# EspBreakoutBoard.net
KiCad netlist of a schematic drawn in EAGLE
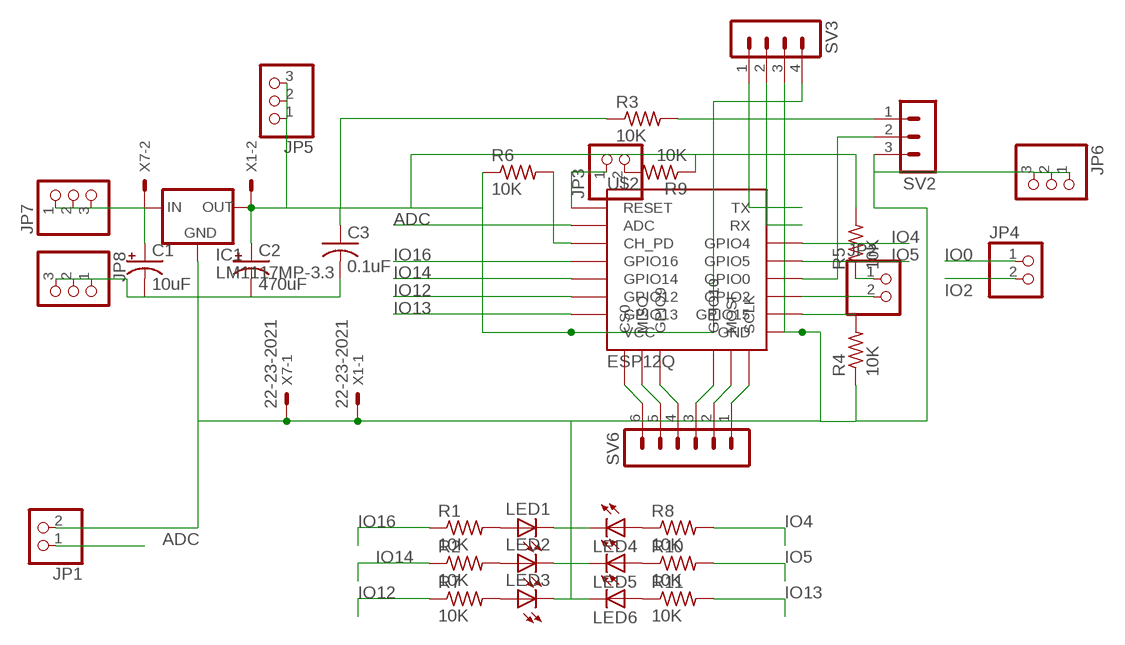
[diagram p0: schematic, sheet 1]

(export (version "E")
  (design (tool "Eeschema 10.0.6"))
  (components
    (comp (ref "C1")
      (value "10uF")
      (footprint "eagle-import:E2,5-6")
      (libsource (lib "eagle-import") (part "CPOL-USE2.5-6"))
    )
    (comp (ref "C2")
      (value "470uF")
      (footprint "eagle-import:E5-8,5")
      (libsource (lib "eagle-import") (part "CPOL-USE5-8.5"))
    )
    (comp (ref "C3")
      (value "0.1uF")
      (footprint "eagle-import:C025-040X050")
      (libsource (lib "eagle-import") (part "C-US025-040X050"))
    )
    (comp (ref "IC1")
      (value "LM1117MP-3.3")
      (footprint "eagle-import:SOT223")
      (fields (field (name "MF") "Texas Instruments"))
      (libsource (lib "eagle-import") (part "LM1117?-MP3.3"))
    )
    (comp (ref "JP1")
      (value "PINHD-1X2")
      (footprint "eagle-import:1X02")
      (libsource (lib "eagle-import") (part "PINHD-1X2"))
    )
    (comp (ref "JP2")
      (value "PINHD-1X2")
      (footprint "eagle-import:1X02")
      (libsource (lib "eagle-import") (part "PINHD-1X2"))
    )
    (comp (ref "JP3")
      (value "PINHD-1X2")
      (footprint "eagle-import:1X02")
      (libsource (lib "eagle-import") (part "PINHD-1X2"))
    )
    (comp (ref "JP4")
      (value "PINHD-1X2")
      (footprint "eagle-import:1X02")
      (libsource (lib "eagle-import") (part "PINHD-1X2"))
    )
    (comp (ref "JP5")
      (value "PINHD-1X3")
      (footprint "eagle-import:1X03")
      (libsource (lib "eagle-import") (part "PINHD-1X3"))
    )
    (comp (ref "JP6")
      (value "PINHD-1X3")
      (footprint "eagle-import:1X03")
      (libsource (lib "eagle-import") (part "PINHD-1X3"))
    )
    (comp (ref "JP7")
      (value "PINHD-1X3")
      (footprint "eagle-import:1X03")
      (libsource (lib "eagle-import") (part "PINHD-1X3"))
    )
    (comp (ref "JP8")
      (value "PINHD-1X3")
      (footprint "eagle-import:1X03")
      (libsource (lib "eagle-import") (part "PINHD-1X3"))
    )
    (comp (ref "LED1")
      (value "LED3MM")
      (footprint "eagle-import:LED3MM")
      (libsource (lib "eagle-import") (part "LED3MM"))
    )
    (comp (ref "LED2")
      (value "LED3MM")
      (footprint "eagle-import:LED3MM")
      (libsource (lib "eagle-import") (part "LED3MM"))
    )
    (comp (ref "LED3")
      (value "LED3MM")
      (footprint "eagle-import:LED3MM")
      (libsource (lib "eagle-import") (part "LED3MM"))
    )
    (comp (ref "LED4")
      (value "LED3MM")
      (footprint "eagle-import:LED3MM")
      (libsource (lib "eagle-import") (part "LED3MM"))
    )
    (comp (ref "LED5")
      (value "LED3MM")
      (footprint "eagle-import:LED3MM")
      (libsource (lib "eagle-import") (part "LED3MM"))
    )
    (comp (ref "LED6")
      (value "LED3MM")
      (footprint "eagle-import:LED3MM")
      (libsource (lib "eagle-import") (part "LED3MM"))
    )
    (comp (ref "R1")
      (value "10K")
      (footprint "eagle-import:0207_10")
      (libsource (lib "eagle-import") (part "R-US_0207/10"))
    )
    (comp (ref "R2")
      (value "10K")
      (footprint "eagle-import:0207_10")
      (libsource (lib "eagle-import") (part "R-US_0207/10"))
    )
    (comp (ref "R3")
      (value "10K")
      (footprint "eagle-import:0207_10")
      (libsource (lib "eagle-import") (part "R-US_0207/10"))
    )
    (comp (ref "R4")
      (value "10K")
      (footprint "eagle-import:0207_10")
      (libsource (lib "eagle-import") (part "R-US_0207/10"))
    )
    (comp (ref "R5")
      (value "10K")
      (footprint "eagle-import:0207_10")
      (libsource (lib "eagle-import") (part "R-US_0207/10"))
    )
    (comp (ref "R6")
      (value "10K")
      (footprint "eagle-import:0207_10")
      (libsource (lib "eagle-import") (part "R-US_0207/10"))
    )
    (comp (ref "R7")
      (value "10K")
      (footprint "eagle-import:0207_10")
      (libsource (lib "eagle-import") (part "R-US_0207/10"))
    )
    (comp (ref "R8")
      (value "10K")
      (footprint "eagle-import:0207_10")
      (libsource (lib "eagle-import") (part "R-US_0207/10"))
    )
    (comp (ref "R9")
      (value "10K")
      (footprint "eagle-import:0207_10")
      (libsource (lib "eagle-import") (part "R-US_0207/10"))
    )
    (comp (ref "R10")
      (value "10K")
      (footprint "eagle-import:0207_10")
      (libsource (lib "eagle-import") (part "R-US_0207/10"))
    )
    (comp (ref "R11")
      (value "10K")
      (footprint "eagle-import:0207_10")
      (libsource (lib "eagle-import") (part "R-US_0207/10"))
    )
    (comp (ref "SV2")
      (value "MA03-1")
      (footprint "eagle-import:MA03-1")
      (libsource (lib "eagle-import") (part "MA03-1"))
    )
    (comp (ref "SV3")
      (value "MA04-1")
      (footprint "eagle-import:MA04-1")
      (libsource (lib "eagle-import") (part "MA04-1"))
    )
    (comp (ref "SV6")
      (value "MA06-1")
      (footprint "eagle-import:MA06-1")
      (libsource (lib "eagle-import") (part "MA06-1"))
    )
    (comp (ref "U$2")
      (value "ESP12Q")
      (footprint "eagle-import:ESP12Q")
      (libsource (lib "eagle-import") (part "ESP12Q"))
    )
    (comp (ref "X1")
      (value "22-23-2021")
      (footprint "eagle-import:22-23-2021")
      (fields (field (name "MF") "MOLEX"))
      (libsource (lib "eagle-import") (part "22-23-2021"))
    )
    (comp (ref "X7")
      (value "22-23-2021")
      (footprint "eagle-import:22-23-2021")
      (fields (field (name "MF") "MOLEX"))
      (libsource (lib "eagle-import") (part "22-23-2021"))
    )
  )
  (nets
    (net (code "1") (name "/ADC") (class "Default")
      (node (ref "JP1") (pin "1") (pinfunction "1_1") (pintype "passive"))
      (node (ref "U$2") (pin "ADC") (pinfunction "ADC_ADC") (pintype "bidirectional"))
    )
    (net (code "2") (name "/IO0") (class "Default")
      (node (ref "JP4") (pin "1") (pinfunction "1_1") (pintype "passive"))
      (node (ref "SV2") (pin "2") (pinfunction "2_2") (pintype "passive"))
      (node (ref "U$2") (pin "GPIO0") (pinfunction "GPIO0_GPIO0") (pintype "bidirectional"))
    )
    (net (code "3") (name "/IO2") (class "Default")
      (node (ref "JP2") (pin "2") (pinfunction "2_2") (pintype "passive"))
      (node (ref "JP4") (pin "2") (pinfunction "2_2") (pintype "passive"))
      (node (ref "U$2") (pin "GPIO2") (pinfunction "GPIO2_GPIO2") (pintype "bidirectional"))
    )
    (net (code "4") (name "/IO4") (class "Default")
      (node (ref "R8") (pin "2") (pinfunction "2_2") (pintype "passive"))
      (node (ref "U$2") (pin "GPIO4") (pinfunction "GPIO4_GPIO4") (pintype "bidirectional"))
    )
    (net (code "5") (name "/IO5") (class "Default")
      (node (ref "R10") (pin "2") (pinfunction "2_2") (pintype "passive"))
      (node (ref "U$2") (pin "GPIO5") (pinfunction "GPIO5_GPIO5") (pintype "bidirectional"))
    )
    (net (code "6") (name "/IO12") (class "Default")
      (node (ref "R7") (pin "1") (pinfunction "1_1") (pintype "passive"))
      (node (ref "U$2") (pin "GPIO12") (pinfunction "GPIO12_GPIO12") (pintype "bidirectional"))
    )
    (net (code "7") (name "/IO13") (class "Default")
      (node (ref "R11") (pin "2") (pinfunction "2_2") (pintype "passive"))
      (node (ref "U$2") (pin "GPIO13") (pinfunction "GPIO13_GPIO13") (pintype "bidirectional"))
    )
    (net (code "8") (name "/IO14") (class "Default")
      (node (ref "R2") (pin "1") (pinfunction "1_1") (pintype "passive"))
      (node (ref "U$2") (pin "GPIO14") (pinfunction "GPIO14_GPIO14") (pintype "bidirectional"))
    )
    (net (code "9") (name "/IO16") (class "Default")
      (node (ref "R1") (pin "1") (pinfunction "1_1") (pintype "passive"))
      (node (ref "U$2") (pin "GPIO16") (pinfunction "GPIO16_GPIO16") (pintype "bidirectional"))
    )
    (net (code "10") (name "Net-(IC1-GND)") (class "Default")
      (node (ref "C1") (pin "-") (pinfunction "-_-") (pintype "passive"))
      (node (ref "C2") (pin "-") (pinfunction "-_-") (pintype "passive"))
      (node (ref "C3") (pin "2") (pinfunction "2_2") (pintype "passive"))
      (node (ref "IC1") (pin "1") (pinfunction "GND_1") (pintype "input"))
      (node (ref "JP1") (pin "2") (pinfunction "2_2") (pintype "passive"))
      (node (ref "JP6") (pin "1") (pinfunction "1_1") (pintype "passive"))
      (node (ref "JP6") (pin "2") (pinfunction "2_2") (pintype "passive"))
      (node (ref "JP6") (pin "3") (pinfunction "3_3") (pintype "passive"))
      (node (ref "JP8") (pin "1") (pinfunction "1_1") (pintype "passive"))
      (node (ref "JP8") (pin "2") (pinfunction "2_2") (pintype "passive"))
      (node (ref "JP8") (pin "3") (pinfunction "3_3") (pintype "passive"))
      (node (ref "LED1") (pin "K") (pinfunction "C_K") (pintype "passive"))
      (node (ref "LED2") (pin "K") (pinfunction "C_K") (pintype "passive"))
      (node (ref "LED3") (pin "K") (pinfunction "C_K") (pintype "passive"))
      (node (ref "LED4") (pin "K") (pinfunction "C_K") (pintype "passive"))
      (node (ref "LED5") (pin "K") (pinfunction "C_K") (pintype "passive"))
      (node (ref "LED6") (pin "K") (pinfunction "C_K") (pintype "passive"))
      (node (ref "R4") (pin "1") (pinfunction "1_1") (pintype "passive"))
      (node (ref "SV2") (pin "3") (pinfunction "3_3") (pintype "passive"))
      (node (ref "SV3") (pin "3") (pinfunction "3_3") (pintype "passive"))
      (node (ref "U$2") (pin "GND") (pinfunction "GND_GND") (pintype "bidirectional"))
      (node (ref "X1") (pin "1") (pinfunction "S_1") (pintype "passive"))
      (node (ref "X7") (pin "1") (pinfunction "S_1") (pintype "passive"))
    )
    (net (code "11") (name "Net-(IC1-IN)") (class "Default")
      (node (ref "C1") (pin "+") (pinfunction "+_+") (pintype "passive"))
      (node (ref "IC1") (pin "3") (pinfunction "IN_3") (pintype "input"))
      (node (ref "JP7") (pin "1") (pinfunction "1_1") (pintype "passive"))
      (node (ref "JP7") (pin "2") (pinfunction "2_2") (pintype "passive"))
      (node (ref "JP7") (pin "3") (pinfunction "3_3") (pintype "passive"))
      (node (ref "X7") (pin "2") (pinfunction "S_2") (pintype "passive"))
    )
    (net (code "12") (name "Net-(JP2-Pad1)") (class "Default")
      (node (ref "JP2") (pin "1") (pinfunction "1_1") (pintype "passive"))
      (node (ref "R5") (pin "1") (pinfunction "1_1") (pintype "passive"))
    )
    (net (code "13") (name "Net-(JP3-Pad1)") (class "Default")
      (node (ref "JP3") (pin "1") (pinfunction "1_1") (pintype "passive"))
      (node (ref "U$2") (pin "RESET") (pinfunction "RESET_RESET") (pintype "bidirectional"))
    )
    (net (code "14") (name "Net-(JP3-Pad2)") (class "Default")
      (node (ref "JP3") (pin "2") (pinfunction "2_2") (pintype "passive"))
      (node (ref "R9") (pin "2") (pinfunction "2_2") (pintype "passive"))
    )
    (net (code "15") (name "Net-(LED1-PadA)") (class "Default")
      (node (ref "LED1") (pin "A") (pinfunction "A_A") (pintype "passive"))
      (node (ref "R1") (pin "2") (pinfunction "2_2") (pintype "passive"))
    )
    (net (code "16") (name "Net-(LED2-PadA)") (class "Default")
      (node (ref "LED2") (pin "A") (pinfunction "A_A") (pintype "passive"))
      (node (ref "R2") (pin "2") (pinfunction "2_2") (pintype "passive"))
    )
    (net (code "17") (name "Net-(LED3-PadA)") (class "Default")
      (node (ref "LED3") (pin "A") (pinfunction "A_A") (pintype "passive"))
      (node (ref "R7") (pin "2") (pinfunction "2_2") (pintype "passive"))
    )
    (net (code "18") (name "Net-(LED4-PadA)") (class "Default")
      (node (ref "LED4") (pin "A") (pinfunction "A_A") (pintype "passive"))
      (node (ref "R8") (pin "1") (pinfunction "1_1") (pintype "passive"))
    )
    (net (code "19") (name "Net-(LED5-PadA)") (class "Default")
      (node (ref "LED5") (pin "A") (pinfunction "A_A") (pintype "passive"))
      (node (ref "R10") (pin "1") (pinfunction "1_1") (pintype "passive"))
    )
    (net (code "20") (name "Net-(LED6-PadA)") (class "Default")
      (node (ref "LED6") (pin "A") (pinfunction "A_A") (pintype "passive"))
      (node (ref "R11") (pin "1") (pinfunction "1_1") (pintype "passive"))
    )
    (net (code "21") (name "Net-(R3-Pad2)") (class "Default")
      (node (ref "R3") (pin "2") (pinfunction "2_2") (pintype "passive"))
      (node (ref "SV2") (pin "1") (pinfunction "1_1") (pintype "passive"))
    )
    (net (code "22") (name "Net-(R4-Pad2)") (class "Default")
      (node (ref "R4") (pin "2") (pinfunction "2_2") (pintype "passive"))
      (node (ref "U$2") (pin "GPIO15") (pinfunction "GPIO15_GPIO15") (pintype "bidirectional"))
    )
    (net (code "23") (name "Net-(R6-Pad2)") (class "Default")
      (node (ref "R6") (pin "2") (pinfunction "2_2") (pintype "passive"))
      (node (ref "U$2") (pin "CH_PD") (pinfunction "CH_PD_CH_PD") (pintype "bidirectional"))
    )
    (net (code "24") (name "Net-(SV3-Pad1)") (class "Default")
      (node (ref "SV3") (pin "1") (pinfunction "1_1") (pintype "passive"))
      (node (ref "U$2") (pin "TX") (pinfunction "TX_TX") (pintype "bidirectional"))
    )
    (net (code "25") (name "Net-(SV3-Pad2)") (class "Default")
      (node (ref "SV3") (pin "2") (pinfunction "2_2") (pintype "passive"))
      (node (ref "U$2") (pin "RX") (pinfunction "RX_RX") (pintype "bidirectional"))
    )
    (net (code "26") (name "Net-(SV6-Pad1)") (class "Default")
      (node (ref "SV6") (pin "1") (pinfunction "1_1") (pintype "passive"))
      (node (ref "U$2") (pin "SCLK") (pinfunction "SCLK_SCLK") (pintype "bidirectional"))
    )
    (net (code "27") (name "Net-(SV6-Pad2)") (class "Default")
      (node (ref "SV6") (pin "2") (pinfunction "2_2") (pintype "passive"))
      (node (ref "U$2") (pin "MOSI") (pinfunction "MOSI_MOSI") (pintype "bidirectional"))
    )
    (net (code "28") (name "Net-(SV6-Pad3)") (class "Default")
      (node (ref "SV6") (pin "3") (pinfunction "3_3") (pintype "passive"))
      (node (ref "U$2") (pin "GPIO10") (pinfunction "GPIO10_GPIO10") (pintype "bidirectional"))
    )
    (net (code "29") (name "Net-(SV6-Pad4)") (class "Default")
      (node (ref "SV6") (pin "4") (pinfunction "4_4") (pintype "passive"))
      (node (ref "U$2") (pin "GPIO9") (pinfunction "GPIO9_GPIO9") (pintype "bidirectional"))
    )
    (net (code "30") (name "Net-(SV6-Pad5)") (class "Default")
      (node (ref "SV6") (pin "5") (pinfunction "5_5") (pintype "passive"))
      (node (ref "U$2") (pin "MISO") (pinfunction "MISO_MISO") (pintype "bidirectional"))
    )
    (net (code "31") (name "Net-(SV6-Pad6)") (class "Default")
      (node (ref "SV6") (pin "6") (pinfunction "6_6") (pintype "passive"))
      (node (ref "U$2") (pin "CS0") (pinfunction "CS0_CS0") (pintype "bidirectional"))
    )
    (net (code "32") (name "Net-(X1B-S)") (class "Default")
      (node (ref "C2") (pin "+") (pinfunction "+_+") (pintype "passive"))
      (node (ref "C3") (pin "1") (pinfunction "1_1") (pintype "passive"))
      (node (ref "IC1") (pin "2") (pinfunction "OUT_2") (pintype "passive"))
      (node (ref "IC1") (pin "4") (pinfunction "OUT_4") (pintype "passive"))
      (node (ref "JP5") (pin "1") (pinfunction "1_1") (pintype "passive"))
      (node (ref "JP5") (pin "2") (pinfunction "2_2") (pintype "passive"))
      (node (ref "JP5") (pin "3") (pinfunction "3_3") (pintype "passive"))
      (node (ref "R3") (pin "1") (pinfunction "1_1") (pintype "passive"))
      (node (ref "R5") (pin "2") (pinfunction "2_2") (pintype "passive"))
      (node (ref "R6") (pin "1") (pinfunction "1_1") (pintype "passive"))
      (node (ref "R9") (pin "1") (pinfunction "1_1") (pintype "passive"))
      (node (ref "SV3") (pin "4") (pinfunction "4_4") (pintype "passive"))
      (node (ref "U$2") (pin "VCC") (pinfunction "VCC_VCC") (pintype "bidirectional"))
      (node (ref "X1") (pin "2") (pinfunction "S_2") (pintype "passive"))
    )
  )
)
